# Motor_Driver.net
KiCad netlist of a schematic drawn in EAGLE
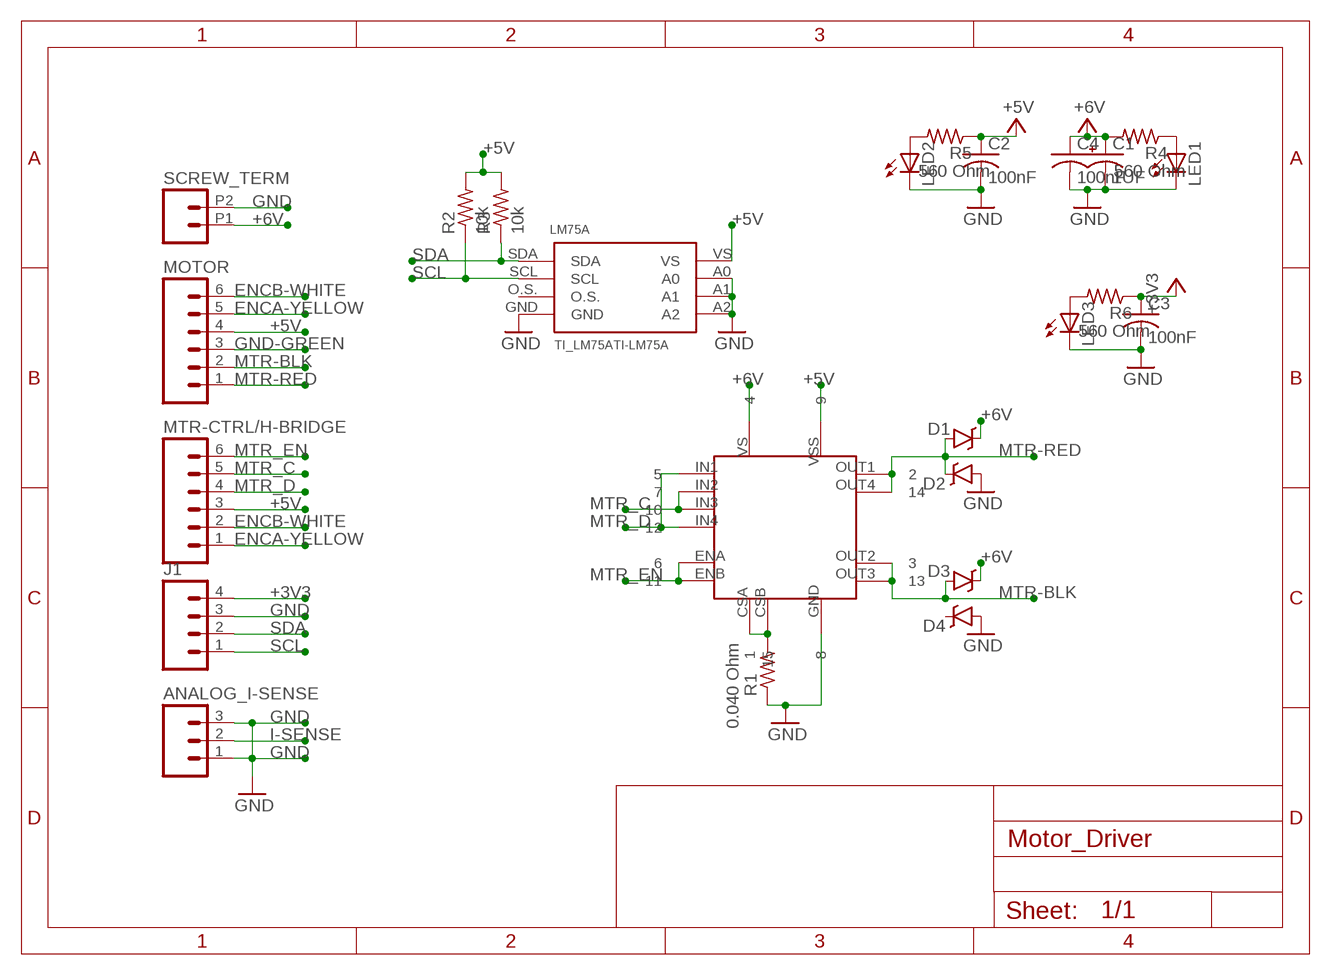
[diagram p0: schematic, sheet 1]

(export (version "E")
  (design (tool "Eeschema 10.0.6"))
  (components
    (comp (ref "ANALOG_I-SENSE")
      (value "M03PTH")
      (footprint "eagle-import:1X03")
      (libsource (lib "eagle-import") (part "M03PTH"))
    )
    (comp (ref "C1")
      (value "1UF")
      (footprint "eagle-import:CPOL-RADIAL-1UF-50V-KIT")
      (libsource (lib "eagle-import") (part "1UF-50V-20%(PTH)KIT"))
    )
    (comp (ref "C2")
      (value "100nF")
      (footprint "eagle-import:C1206")
      (libsource (lib "eagle-import") (part "C-USC1206"))
    )
    (comp (ref "C3")
      (value "100nF")
      (footprint "eagle-import:C1206")
      (libsource (lib "eagle-import") (part "C-USC1206"))
    )
    (comp (ref "C4")
      (value "100nF")
      (footprint "eagle-import:C1206")
      (libsource (lib "eagle-import") (part "C-USC1206"))
    )
    (comp (ref "D1")
      (value "B340A")
      (footprint "eagle-import:SMA-DIODE")
      (libsource (lib "eagle-import") (part "DIODE-SCHOTTKY-B340A"))
    )
    (comp (ref "D2")
      (value "B340A")
      (footprint "eagle-import:SMA-DIODE")
      (libsource (lib "eagle-import") (part "DIODE-SCHOTTKY-B340A"))
    )
    (comp (ref "D3")
      (value "B340A")
      (footprint "eagle-import:SMA-DIODE")
      (libsource (lib "eagle-import") (part "DIODE-SCHOTTKY-B340A"))
    )
    (comp (ref "D4")
      (value "B340A")
      (footprint "eagle-import:SMA-DIODE")
      (libsource (lib "eagle-import") (part "DIODE-SCHOTTKY-B340A"))
    )
    (comp (ref "J1")
      (value "M04PTH")
      (footprint "eagle-import:1X04")
      (libsource (lib "eagle-import") (part "M04PTH"))
    )
    (comp (ref "LED1")
      (value "LEDSMT1206")
      (footprint "eagle-import:1206")
      (libsource (lib "eagle-import") (part "LEDSMT1206"))
    )
    (comp (ref "LED2")
      (value "LEDSMT1206")
      (footprint "eagle-import:1206")
      (libsource (lib "eagle-import") (part "LEDSMT1206"))
    )
    (comp (ref "LED3")
      (value "LEDSMT1206")
      (footprint "eagle-import:1206")
      (libsource (lib "eagle-import") (part "LEDSMT1206"))
    )
    (comp (ref "LM75A")
      (value "TI_LM75ATI-LM75A")
      (footprint "eagle-import:TI_LM75A")
      (libsource (lib "eagle-import") (part "TI_LM75ATI-LM75A"))
    )
    (comp (ref "MOTOR")
      (value "M06SILK_FEMALE_PTH")
      (footprint "eagle-import:1X06")
      (libsource (lib "eagle-import") (part "M06SILK_FEMALE_PTH"))
    )
    (comp (ref "MTR-CTRL/H-BRIDGE")
      (value "M06SILK_FEMALE_PTH")
      (footprint "eagle-import:1X06")
      (libsource (lib "eagle-import") (part "M06SILK_FEMALE_PTH"))
    )
    (comp (ref "R1")
      (value "0.040 Ohm")
      (footprint "eagle-import:M0805")
      (libsource (lib "eagle-import") (part "R-US_M0805"))
    )
    (comp (ref "R2")
      (value "10k")
      (footprint "eagle-import:M1206")
      (libsource (lib "eagle-import") (part "R-US_M1206"))
    )
    (comp (ref "R3")
      (value "10k")
      (footprint "eagle-import:M1206")
      (libsource (lib "eagle-import") (part "R-US_M1206"))
    )
    (comp (ref "R4")
      (value "560 Ohm")
      (footprint "eagle-import:M0805")
      (libsource (lib "eagle-import") (part "R-US_M0805"))
    )
    (comp (ref "R5")
      (value "560 Ohm")
      (footprint "eagle-import:M0805")
      (libsource (lib "eagle-import") (part "R-US_M0805"))
    )
    (comp (ref "R6")
      (value "560 Ohm")
      (footprint "eagle-import:M0805")
      (libsource (lib "eagle-import") (part "R-US_M0805"))
    )
    (comp (ref "SCREW_TERM")
      (value "M022.54MM_SCREWTERM")
      (footprint "eagle-import:1X02_2.54_SCREWTERM")
      (libsource (lib "eagle-import") (part "M022.54MM_SCREWTERM"))
    )
    (comp (ref "U$1")
      (value "STL298N")
      (footprint "eagle-import:STL298N")
      (libsource (lib "eagle-import") (part "STL298N"))
    )
  )
  (nets
    (net (code "1") (name "+3V3") (class "Default")
      (node (ref "C3") (pin "1") (pinfunction "1_1") (pintype "passive"))
      (node (ref "J1") (pin "4") (pinfunction "4_4") (pintype "passive"))
      (node (ref "R6") (pin "1") (pinfunction "1_1") (pintype "passive"))
    )
    (net (code "2") (name "+5V") (class "Default")
      (node (ref "C2") (pin "1") (pinfunction "1_1") (pintype "passive"))
      (node (ref "LM75A") (pin "VS") (pinfunction "VS_VS") (pintype "bidirectional"))
      (node (ref "MOTOR") (pin "4") (pinfunction "4_4") (pintype "passive"))
      (node (ref "MTR-CTRL/H-BRIDGE") (pin "3") (pinfunction "3_3") (pintype "passive"))
      (node (ref "R2") (pin "2") (pinfunction "2_2") (pintype "passive"))
      (node (ref "R3") (pin "2") (pinfunction "2_2") (pintype "passive"))
      (node (ref "R5") (pin "1") (pinfunction "1_1") (pintype "passive"))
    )
    (net (code "3") (name "+6V") (class "Default")
      (node (ref "C1") (pin "1") (pinfunction "+_1") (pintype "passive"))
      (node (ref "C4") (pin "1") (pinfunction "1_1") (pintype "passive"))
      (node (ref "D1") (pin "C") (pinfunction "C_C") (pintype "passive"))
      (node (ref "D3") (pin "C") (pinfunction "C_C") (pintype "passive"))
      (node (ref "R4") (pin "2") (pinfunction "2_2") (pintype "passive"))
      (node (ref "SCREW_TERM") (pin "P1") (pinfunction "1_P1") (pintype "passive"))
    )
    (net (code "4") (name "/ENCA-YELLOW") (class "Default")
      (node (ref "MOTOR") (pin "5") (pinfunction "5_5") (pintype "passive"))
      (node (ref "MTR-CTRL/H-BRIDGE") (pin "1") (pinfunction "1_1") (pintype "passive"))
    )
    (net (code "5") (name "/ENCB-WHITE") (class "Default")
      (node (ref "MOTOR") (pin "6") (pinfunction "6_6") (pintype "passive"))
      (node (ref "MTR-CTRL/H-BRIDGE") (pin "2") (pinfunction "2_2") (pintype "passive"))
    )
    (net (code "6") (name "/GND-GREEN") (class "Default")
      (node (ref "MOTOR") (pin "3") (pinfunction "3_3") (pintype "passive"))
    )
    (net (code "7") (name "/I-SENSE") (class "Default")
      (node (ref "ANALOG_I-SENSE") (pin "2") (pinfunction "2_2") (pintype "passive"))
    )
    (net (code "8") (name "/MTR-BLK") (class "Default")
      (node (ref "D3") (pin "A") (pinfunction "A_A") (pintype "passive"))
      (node (ref "MOTOR") (pin "2") (pinfunction "2_2") (pintype "passive"))
    )
    (net (code "9") (name "/MTR-RED") (class "Default")
      (node (ref "D1") (pin "A") (pinfunction "A_A") (pintype "passive"))
      (node (ref "D2") (pin "C") (pinfunction "C_C") (pintype "passive"))
      (node (ref "MOTOR") (pin "1") (pinfunction "1_1") (pintype "passive"))
    )
    (net (code "10") (name "/MTR_C") (class "Default")
      (node (ref "MTR-CTRL/H-BRIDGE") (pin "5") (pinfunction "5_5") (pintype "passive"))
    )
    (net (code "11") (name "/MTR_D") (class "Default")
      (node (ref "MTR-CTRL/H-BRIDGE") (pin "4") (pinfunction "4_4") (pintype "passive"))
    )
    (net (code "12") (name "/MTR_EN") (class "Default")
      (node (ref "MTR-CTRL/H-BRIDGE") (pin "6") (pinfunction "6_6") (pintype "passive"))
    )
    (net (code "13") (name "/SCL") (class "Default")
      (node (ref "J1") (pin "1") (pinfunction "1_1") (pintype "passive"))
      (node (ref "LM75A") (pin "SCL") (pinfunction "SCL_SCL") (pintype "bidirectional"))
      (node (ref "R2") (pin "1") (pinfunction "1_1") (pintype "passive"))
    )
    (net (code "14") (name "/SDA") (class "Default")
      (node (ref "J1") (pin "2") (pinfunction "2_2") (pintype "passive"))
      (node (ref "LM75A") (pin "SDA") (pinfunction "SDA_SDA") (pintype "bidirectional"))
      (node (ref "R3") (pin "1") (pinfunction "1_1") (pintype "passive"))
    )
    (net (code "15") (name "GND") (class "Default")
      (node (ref "ANALOG_I-SENSE") (pin "1") (pinfunction "1_1") (pintype "passive"))
      (node (ref "ANALOG_I-SENSE") (pin "3") (pinfunction "3_3") (pintype "passive"))
      (node (ref "C1") (pin "2") (pinfunction "-_2") (pintype "passive"))
      (node (ref "C2") (pin "2") (pinfunction "2_2") (pintype "passive"))
      (node (ref "C3") (pin "2") (pinfunction "2_2") (pintype "passive"))
      (node (ref "C4") (pin "2") (pinfunction "2_2") (pintype "passive"))
      (node (ref "D2") (pin "A") (pinfunction "A_A") (pintype "passive"))
      (node (ref "D4") (pin "A") (pinfunction "A_A") (pintype "passive"))
      (node (ref "J1") (pin "3") (pinfunction "3_3") (pintype "passive"))
      (node (ref "LED1") (pin "C") (pinfunction "C_C") (pintype "passive"))
      (node (ref "LED2") (pin "C") (pinfunction "C_C") (pintype "passive"))
      (node (ref "LED3") (pin "C") (pinfunction "C_C") (pintype "passive"))
      (node (ref "LM75A") (pin "A0") (pinfunction "A0_A0") (pintype "bidirectional"))
      (node (ref "LM75A") (pin "A1") (pinfunction "A1_A1") (pintype "bidirectional"))
      (node (ref "LM75A") (pin "A2") (pinfunction "A2_A2") (pintype "bidirectional"))
      (node (ref "LM75A") (pin "GND") (pinfunction "GND_GND") (pintype "bidirectional"))
      (node (ref "R1") (pin "1") (pinfunction "1_1") (pintype "passive"))
      (node (ref "SCREW_TERM") (pin "P2") (pinfunction "2_P2") (pintype "passive"))
    )
    (net (code "16") (name "Net-(LED1-PadA)") (class "Default")
      (node (ref "LED1") (pin "A") (pinfunction "A_A") (pintype "passive"))
      (node (ref "R4") (pin "1") (pinfunction "1_1") (pintype "passive"))
    )
    (net (code "17") (name "Net-(LED2-PadA)") (class "Default")
      (node (ref "LED2") (pin "A") (pinfunction "A_A") (pintype "passive"))
      (node (ref "R5") (pin "2") (pinfunction "2_2") (pintype "passive"))
    )
    (net (code "18") (name "Net-(LED3-PadA)") (class "Default")
      (node (ref "LED3") (pin "A") (pinfunction "A_A") (pintype "passive"))
      (node (ref "R6") (pin "2") (pinfunction "2_2") (pintype "passive"))
    )
    (net (code "19") (name "unconnected-(D4-PadC)") (class "Default")
      (node (ref "D4") (pin "C") (pinfunction "C_C") (pintype "passive"))
    )
    (net (code "20") (name "unconnected-(LM75A-PadO.S.)") (class "Default")
      (node (ref "LM75A") (pin "O.S.") (pinfunction "O.S._O.S.") (pintype "bidirectional"))
    )
    (net (code "21") (name "unconnected-(R1-Pad2)") (class "Default")
      (node (ref "R1") (pin "2") (pinfunction "2_2") (pintype "passive"))
    )
    (net (code "22") (name "unconnected-(U$1-1-PadCSA)") (class "Default")
      (node (ref "U$1") (pin "CSA") (pinfunction "1_CSA") (pintype "bidirectional"))
    )
    (net (code "23") (name "unconnected-(U$1-2-PadOUT1)") (class "Default")
      (node (ref "U$1") (pin "OUT1") (pinfunction "2_OUT1") (pintype "bidirectional"))
    )
    (net (code "24") (name "unconnected-(U$1-3-PadOUT2)") (class "Default")
      (node (ref "U$1") (pin "OUT2") (pinfunction "3_OUT2") (pintype "bidirectional"))
    )
    (net (code "25") (name "unconnected-(U$1-4-PadVS)") (class "Default")
      (node (ref "U$1") (pin "VS") (pinfunction "4_VS") (pintype "bidirectional"))
    )
    (net (code "26") (name "unconnected-(U$1-5-PadIN1)") (class "Default")
      (node (ref "U$1") (pin "IN1") (pinfunction "5_IN1") (pintype "bidirectional"))
    )
    (net (code "27") (name "unconnected-(U$1-6-PadENA)") (class "Default")
      (node (ref "U$1") (pin "ENA") (pinfunction "6_ENA") (pintype "bidirectional"))
    )
    (net (code "28") (name "unconnected-(U$1-7-PadIN2)") (class "Default")
      (node (ref "U$1") (pin "IN2") (pinfunction "7_IN2") (pintype "bidirectional"))
    )
    (net (code "29") (name "unconnected-(U$1-8-PadGND)") (class "Default")
      (node (ref "U$1") (pin "GND") (pinfunction "8_GND") (pintype "bidirectional"))
    )
    (net (code "30") (name "unconnected-(U$1-9-PadVSS)") (class "Default")
      (node (ref "U$1") (pin "VSS") (pinfunction "9_VSS") (pintype "bidirectional"))
    )
    (net (code "31") (name "unconnected-(U$1-10-PadIN3)") (class "Default")
      (node (ref "U$1") (pin "IN3") (pinfunction "10_IN3") (pintype "bidirectional"))
    )
    (net (code "32") (name "unconnected-(U$1-11-PadENB)") (class "Default")
      (node (ref "U$1") (pin "ENB") (pinfunction "11_ENB") (pintype "bidirectional"))
    )
    (net (code "33") (name "unconnected-(U$1-12-PadIN4)") (class "Default")
      (node (ref "U$1") (pin "IN4") (pinfunction "12_IN4") (pintype "bidirectional"))
    )
    (net (code "34") (name "unconnected-(U$1-13-PadOUT3)") (class "Default")
      (node (ref "U$1") (pin "OUT3") (pinfunction "13_OUT3") (pintype "bidirectional"))
    )
    (net (code "35") (name "unconnected-(U$1-14-PadOUT4)") (class "Default")
      (node (ref "U$1") (pin "OUT4") (pinfunction "14_OUT4") (pintype "bidirectional"))
    )
    (net (code "36") (name "unconnected-(U$1-15-PadCSB)") (class "Default")
      (node (ref "U$1") (pin "CSB") (pinfunction "15_CSB") (pintype "bidirectional"))
    )
  )
)
